# H_bridge.net
KiCad netlist of a schematic drawn in Altium Designer
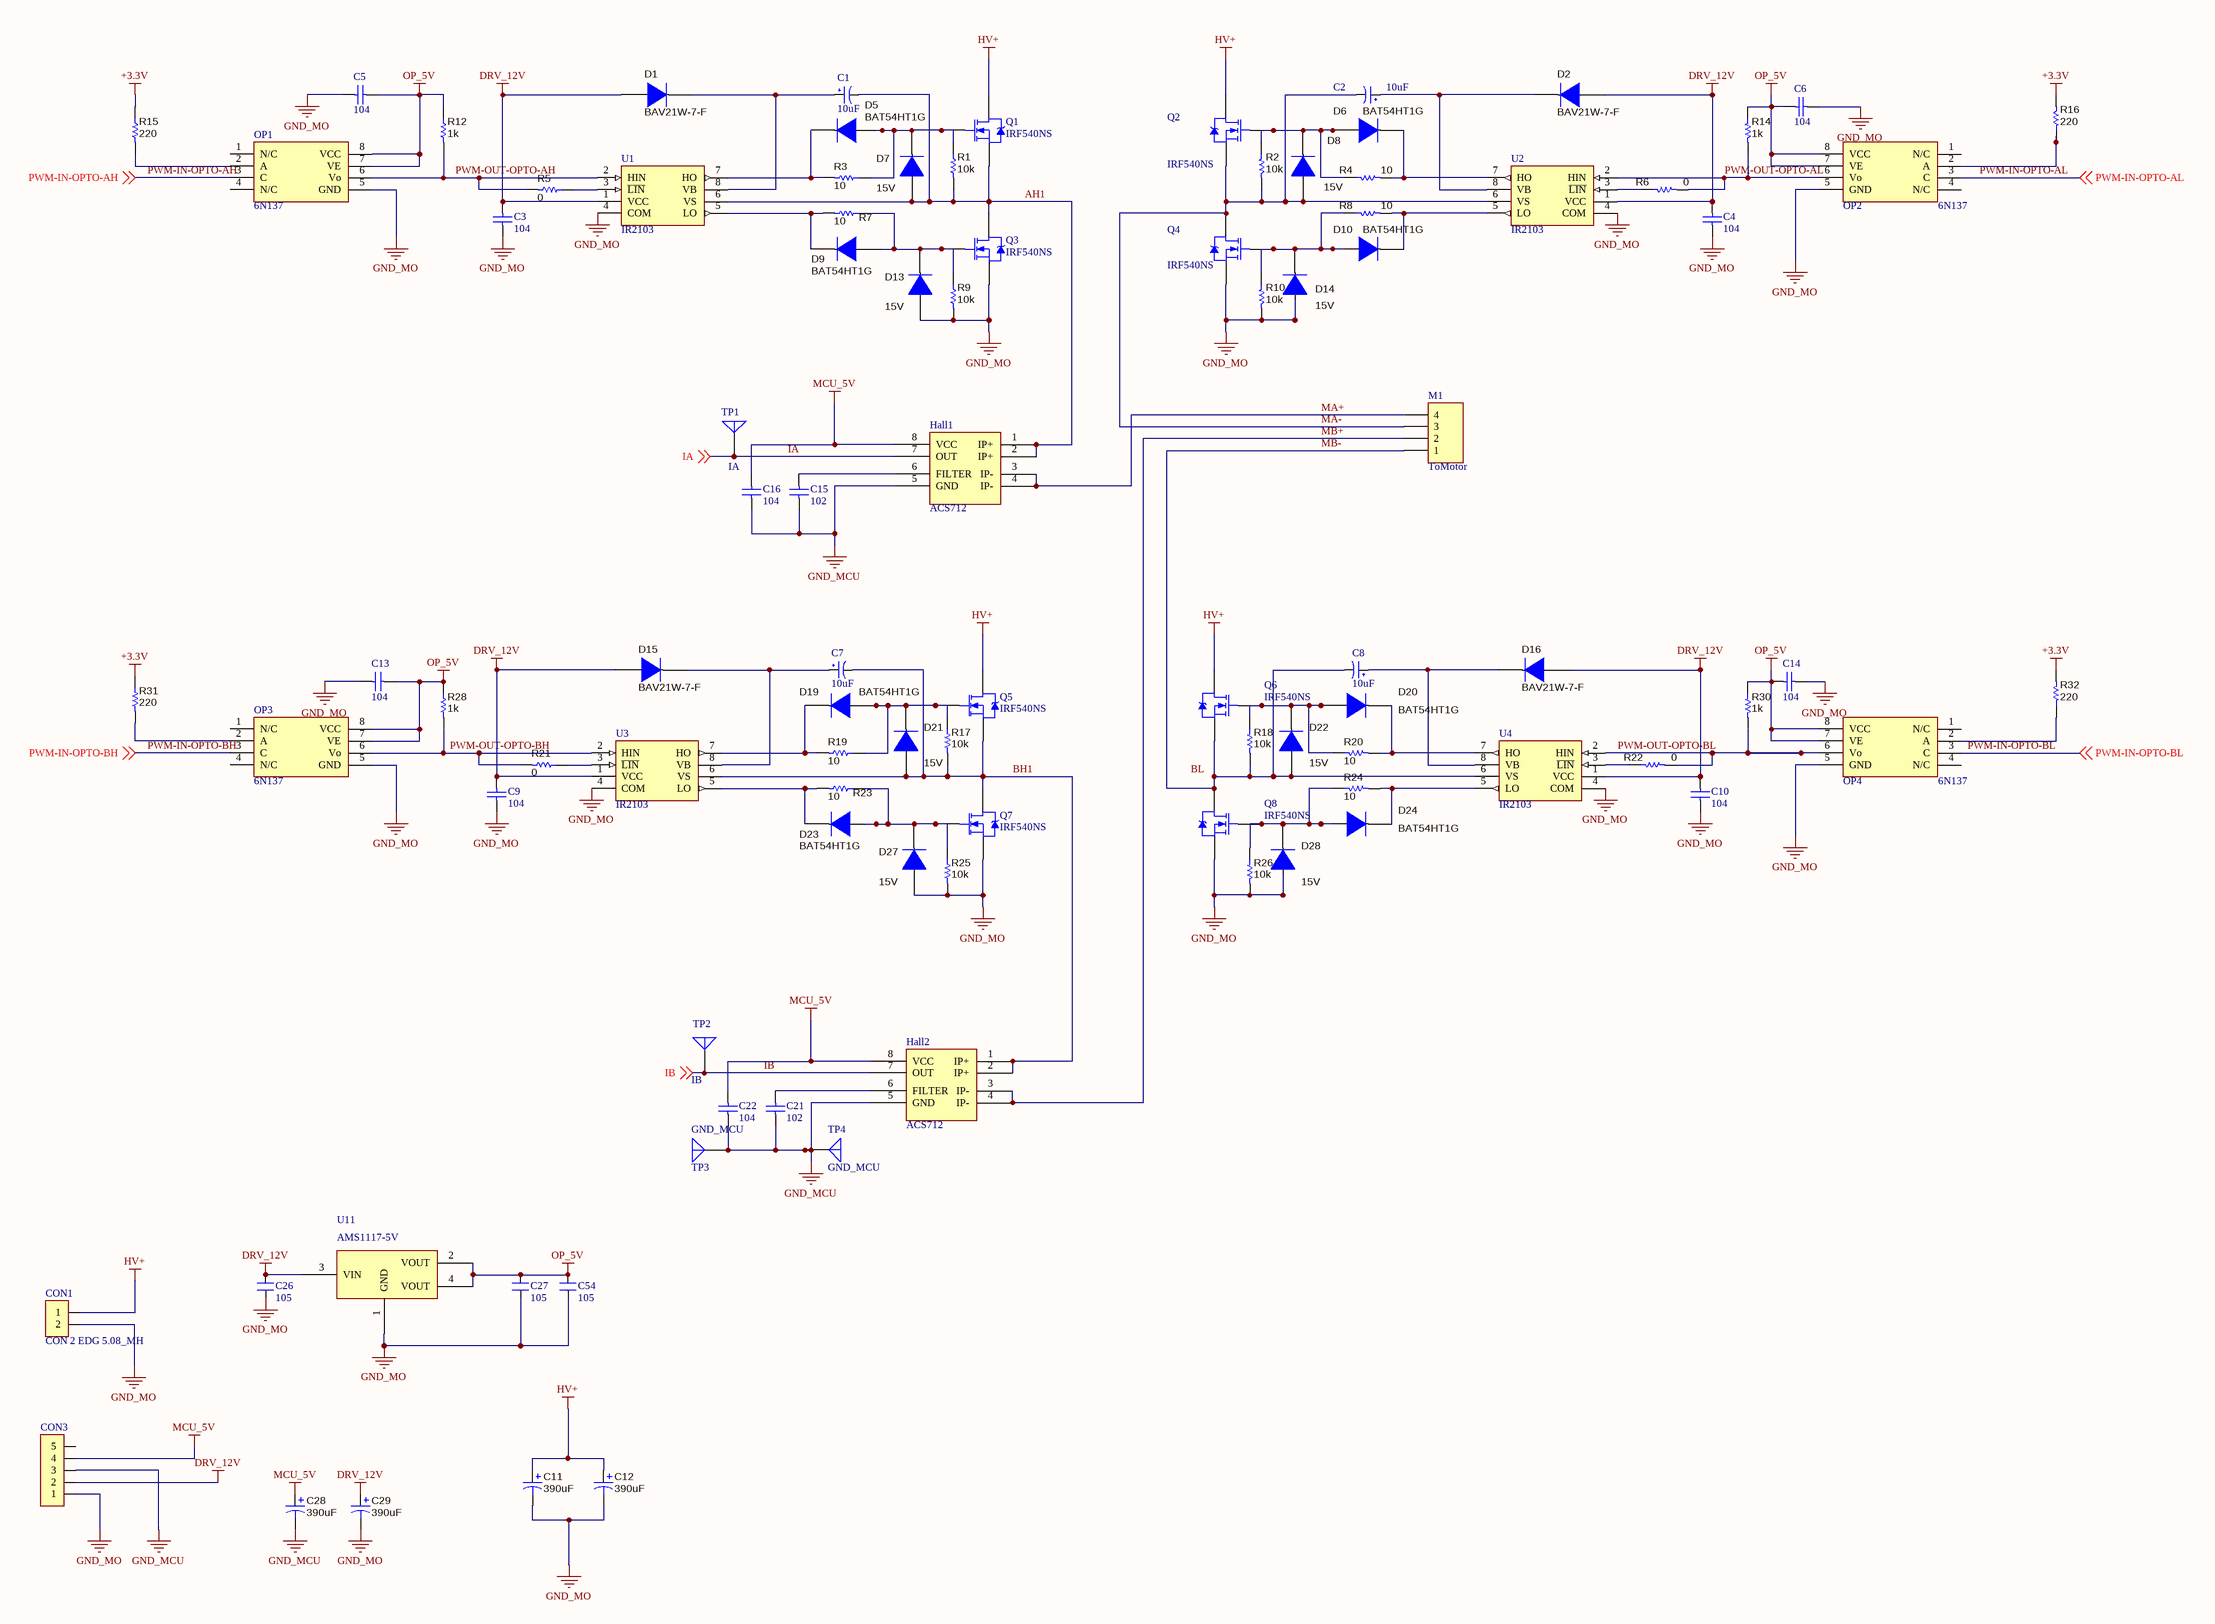
[diagram p0: H_bridge.SchDoc]

(export (version "E")
  (design (tool "Eeschema 10.0.6"))
  (components
    (comp (ref "C1")
      (value "10uF")
      (footprint "TU_NHOM_10uF_MH")
      (description "TU_NHOM_10uF_25V_MH")
      (libsource (lib "MH_DA_THU_VIEN_16122016") (part "TU_NHOM_10uF_25V_MH"))
    )
    (comp (ref "C2")
      (value "10uF")
      (footprint "TU_NHOM_10uF_MH")
      (description "TU_NHOM_10uF_25V_MH")
      (libsource (lib "MH_DA_THU_VIEN_16122016") (part "TU_NHOM_10uF_25V_MH"))
    )
    (comp (ref "C3")
      (value "104")
      (footprint "TU_SMD_0805")
      (description "Ceramic Chip Capacitor - Standard")
      (fields (field (name "PUBLISHER") "Altium Limited"))
      (libsource (lib "mySch") (part "Capacitor 0805"))
    )
    (comp (ref "C4")
      (value "104")
      (footprint "TU_SMD_0805")
      (description "Ceramic Chip Capacitor - Standard")
      (fields (field (name "PUBLISHER") "Altium Limited"))
      (libsource (lib "mySch") (part "Capacitor 0805"))
    )
    (comp (ref "C5")
      (value "104")
      (footprint "TU_SMD_0805")
      (description "Ceramic Chip Capacitor - Standard")
      (fields (field (name "PUBLISHER") "Altium Limited"))
      (libsource (lib "mySch") (part "Capacitor 0805"))
    )
    (comp (ref "C6")
      (value "104")
      (footprint "TU_SMD_0805")
      (description "Ceramic Chip Capacitor - Standard")
      (fields (field (name "PUBLISHER") "Altium Limited"))
      (libsource (lib "mySch") (part "Capacitor 0805"))
    )
    (comp (ref "C7")
      (value "10uF")
      (footprint "TU_NHOM_10uF_MH")
      (description "TU_NHOM_10uF_25V_MH")
      (libsource (lib "MH_DA_THU_VIEN_16122016") (part "TU_NHOM_10uF_25V_MH"))
    )
    (comp (ref "C8")
      (value "10uF")
      (footprint "TU_NHOM_10uF_MH")
      (description "TU_NHOM_10uF_25V_MH")
      (libsource (lib "MH_DA_THU_VIEN_16122016") (part "TU_NHOM_10uF_25V_MH"))
    )
    (comp (ref "C9")
      (value "104")
      (footprint "TU_SMD_0805")
      (description "Ceramic Chip Capacitor - Standard")
      (fields (field (name "PUBLISHER") "Altium Limited"))
      (libsource (lib "mySch") (part "Capacitor 0805"))
    )
    (comp (ref "C10")
      (value "104")
      (footprint "TU_SMD_0805")
      (description "Ceramic Chip Capacitor - Standard")
      (fields (field (name "PUBLISHER") "Altium Limited"))
      (libsource (lib "mySch") (part "Capacitor 0805"))
    )
    (comp (ref "C11")
      (value "390uF")
      (footprint "CAP_12.5 X 25")
      (description "CAP ALUM 390UF 20% 50V RADIAL")
      (fields
        (field (name "PARTNUMBER") "UHW1H391MPD6")
        (field (name "MANUFACTURER") "Nichicon")
        (field (name "VALUEDISPLAYED") "390uF")
        (field (name "PUBLISHER") "Texas Instruments")
      )
      (libsource (lib "mySch") (part "Capacitor TuHoa"))
    )
    (comp (ref "C12")
      (value "390uF")
      (footprint "CAP_12.5 X 25")
      (description "CAP ALUM 390UF 20% 50V RADIAL")
      (fields
        (field (name "PARTNUMBER") "UHW1H391MPD6")
        (field (name "MANUFACTURER") "Nichicon")
        (field (name "VALUEDISPLAYED") "390uF")
        (field (name "PUBLISHER") "Texas Instruments")
      )
      (libsource (lib "mySch") (part "Capacitor TuHoa"))
    )
    (comp (ref "C13")
      (value "104")
      (footprint "TU_SMD_0805")
      (description "Ceramic Chip Capacitor - Standard")
      (fields (field (name "PUBLISHER") "Altium Limited"))
      (libsource (lib "mySch") (part "Capacitor 0805"))
    )
    (comp (ref "C14")
      (value "104")
      (footprint "TU_SMD_0805")
      (description "Ceramic Chip Capacitor - Standard")
      (fields (field (name "PUBLISHER") "Altium Limited"))
      (libsource (lib "mySch") (part "Capacitor 0805"))
    )
    (comp (ref "C15")
      (value "102")
      (footprint "TU_SMD_0805")
      (description "Ceramic Chip Capacitor - Standard")
      (fields (field (name "PUBLISHER") "Altium Limited"))
      (libsource (lib "mySch") (part "Capacitor 0805"))
    )
    (comp (ref "C16")
      (value "104")
      (footprint "TU_SMD_0805")
      (description "Ceramic Chip Capacitor - Standard")
      (fields (field (name "PUBLISHER") "Altium Limited"))
      (libsource (lib "mySch") (part "Capacitor 0805"))
    )
    (comp (ref "C21")
      (value "102")
      (footprint "TU_SMD_0805")
      (description "Ceramic Chip Capacitor - Standard")
      (fields (field (name "PUBLISHER") "Altium Limited"))
      (libsource (lib "mySch") (part "Capacitor 0805"))
    )
    (comp (ref "C22")
      (value "104")
      (footprint "TU_SMD_0805")
      (description "Ceramic Chip Capacitor - Standard")
      (fields (field (name "PUBLISHER") "Altium Limited"))
      (libsource (lib "mySch") (part "Capacitor 0805"))
    )
    (comp (ref "C26")
      (value "105")
      (footprint "0805_HV")
      (description "Cap SMD")
      (libsource (lib "hatcatbietbay") (part "CM"))
    )
    (comp (ref "C27")
      (value "105")
      (footprint "0805_HV")
      (description "Cap SMD")
      (libsource (lib "hatcatbietbay") (part "CM"))
    )
    (comp (ref "C28")
      (value "390uF")
      (footprint "CP1/3.0")
      (fields
        (field (name "PARTNUMBER") "UHW1H391MPD6")
        (field (name "MANUFACTURER") "Nichicon")
        (field (name "VALUEDISPLAYED") "390uF")
        (field (name "PUBLISHER") "Texas Instruments")
      )
      (libsource (lib "mySch") (part "Capacitor TuHoa"))
    )
    (comp (ref "C29")
      (value "390uF")
      (footprint "CP1/3.0")
      (fields
        (field (name "PARTNUMBER") "UHW1H391MPD6")
        (field (name "MANUFACTURER") "Nichicon")
        (field (name "VALUEDISPLAYED") "390uF")
        (field (name "PUBLISHER") "Texas Instruments")
      )
      (libsource (lib "mySch") (part "Capacitor TuHoa"))
    )
    (comp (ref "C54")
      (value "105")
      (footprint "0805_HV")
      (description "Cap SMD")
      (libsource (lib "hatcatbietbay") (part "CM"))
    )
    (comp (ref "CON1")
      (value "CON 2 EDG 5.08_MH")
      (footprint "CON 2 EDG 5.08")
      (description "CON 2 EDG 5.08 (xanh cong)")
      (libsource (lib "mySch") (part "CON 2 EDG 5.08_MH"))
    )
    (comp (ref "CON3")
      (value "CON 5 EDG 5.08_MH")
      (footprint "Con 5 EDG 5.08")
      (description "CON 5 EDG 5.08 (xanh cong)")
      (libsource (lib "MH_DA_THU_VIEN_16122016") (part "CON 5 EDG 5.08_MH"))
    )
    (comp (ref "D1")
      (value "BAV21W-7-F")
      (footprint "SOD-323")
      (description "Diode, Switching, 100 V, 0.2 A, SOD-323")
      (fields
        (field (name "MANUFACTURER") "Micro Commercial Components")
        (field (name "PUBLISHER") "Texas Instruments")
      )
      (libsource (lib "Diode") (part "MMDL914-TP"))
    )
    (comp (ref "D2")
      (value "BAV21W-7-F")
      (footprint "SOD-323")
      (description "Diode, Switching, 100 V, 0.2 A, SOD-323")
      (fields
        (field (name "MANUFACTURER") "Micro Commercial Components")
        (field (name "PUBLISHER") "Texas Instruments")
      )
      (libsource (lib "Diode") (part "MMDL914-TP"))
    )
    (comp (ref "D5")
      (value "BAT54HT1G")
      (footprint "SOD-323")
      (description "Diode, Switching, 100 V, 0.2 A, SOD-323")
      (fields
        (field (name "MANUFACTURER") "Micro Commercial Components")
        (field (name "PUBLISHER") "Texas Instruments")
      )
      (libsource (lib "Diode") (part "MMDL914-TP"))
    )
    (comp (ref "D6")
      (value "BAT54HT1G")
      (footprint "SOD-323")
      (description "Diode, Switching, 100 V, 0.2 A, SOD-323")
      (fields
        (field (name "MANUFACTURER") "Micro Commercial Components")
        (field (name "PUBLISHER") "Texas Instruments")
      )
      (libsource (lib "Diode") (part "MMDL914-TP"))
    )
    (comp (ref "D7")
      (value "15V")
      (footprint "SOD-323")
      (description "Diode, Switching, 100 V, 0.2 A, SOD-323")
      (fields
        (field (name "PARTNUMBER") "BAV21W-7-F")
        (field (name "MANUFACTURER") "Micro Commercial Components")
        (field (name "PUBLISHER") "Texas Instruments")
      )
      (libsource (lib "Diode") (part "MMDL914-TP"))
    )
    (comp (ref "D8")
      (value "15V")
      (footprint "SOD-323")
      (description "Diode, Switching, 100 V, 0.2 A, SOD-323")
      (fields
        (field (name "PARTNUMBER") "BAV21W-7-F")
        (field (name "MANUFACTURER") "Micro Commercial Components")
        (field (name "PUBLISHER") "Texas Instruments")
      )
      (libsource (lib "Diode") (part "MMDL914-TP"))
    )
    (comp (ref "D9")
      (value "BAT54HT1G")
      (footprint "SOD-323")
      (description "Diode, Switching, 100 V, 0.2 A, SOD-323")
      (fields
        (field (name "MANUFACTURER") "Micro Commercial Components")
        (field (name "PUBLISHER") "Texas Instruments")
      )
      (libsource (lib "Diode") (part "MMDL914-TP"))
    )
    (comp (ref "D10")
      (value "BAT54HT1G")
      (footprint "SOD-323")
      (description "Diode, Switching, 100 V, 0.2 A, SOD-323")
      (fields
        (field (name "MANUFACTURER") "Micro Commercial Components")
        (field (name "PUBLISHER") "Texas Instruments")
      )
      (libsource (lib "Diode") (part "MMDL914-TP"))
    )
    (comp (ref "D13")
      (value "15V")
      (footprint "SOD-323")
      (description "Diode, Switching, 100 V, 0.2 A, SOD-323")
      (fields
        (field (name "PARTNUMBER") "BAV21W-7-F")
        (field (name "MANUFACTURER") "Micro Commercial Components")
        (field (name "PUBLISHER") "Texas Instruments")
      )
      (libsource (lib "Diode") (part "MMDL914-TP"))
    )
    (comp (ref "D14")
      (value "15V")
      (footprint "SOD-323")
      (description "Diode, Switching, 100 V, 0.2 A, SOD-323")
      (fields
        (field (name "PARTNUMBER") "BAV21W-7-F")
        (field (name "MANUFACTURER") "Micro Commercial Components")
        (field (name "PUBLISHER") "Texas Instruments")
      )
      (libsource (lib "Diode") (part "MMDL914-TP"))
    )
    (comp (ref "D15")
      (value "BAV21W-7-F")
      (footprint "SOD-323")
      (description "Diode, Switching, 100 V, 0.2 A, SOD-323")
      (fields
        (field (name "MANUFACTURER") "Micro Commercial Components")
        (field (name "PUBLISHER") "Texas Instruments")
      )
      (libsource (lib "Diode") (part "MMDL914-TP"))
    )
    (comp (ref "D16")
      (value "BAV21W-7-F")
      (footprint "SOD-323")
      (description "Diode, Switching, 100 V, 0.2 A, SOD-323")
      (fields
        (field (name "MANUFACTURER") "Micro Commercial Components")
        (field (name "PUBLISHER") "Texas Instruments")
      )
      (libsource (lib "Diode") (part "MMDL914-TP"))
    )
    (comp (ref "D19")
      (value "BAT54HT1G")
      (footprint "SOD-323")
      (description "Diode, Switching, 100 V, 0.2 A, SOD-323")
      (fields
        (field (name "MANUFACTURER") "Micro Commercial Components")
        (field (name "PUBLISHER") "Texas Instruments")
      )
      (libsource (lib "Diode") (part "MMDL914-TP"))
    )
    (comp (ref "D20")
      (value "BAT54HT1G")
      (footprint "SOD-323")
      (description "Diode, Switching, 100 V, 0.2 A, SOD-323")
      (fields
        (field (name "MANUFACTURER") "Micro Commercial Components")
        (field (name "PUBLISHER") "Texas Instruments")
      )
      (libsource (lib "Diode") (part "MMDL914-TP"))
    )
    (comp (ref "D21")
      (value "15V")
      (footprint "SOD-323")
      (description "Diode, Switching, 100 V, 0.2 A, SOD-323")
      (fields
        (field (name "PARTNUMBER") "BAV21W-7-F")
        (field (name "MANUFACTURER") "Micro Commercial Components")
        (field (name "PUBLISHER") "Texas Instruments")
      )
      (libsource (lib "Diode") (part "MMDL914-TP"))
    )
    (comp (ref "D22")
      (value "15V")
      (footprint "SOD-323")
      (description "Diode, Switching, 100 V, 0.2 A, SOD-323")
      (fields
        (field (name "PARTNUMBER") "BAV21W-7-F")
        (field (name "MANUFACTURER") "Micro Commercial Components")
        (field (name "PUBLISHER") "Texas Instruments")
      )
      (libsource (lib "Diode") (part "MMDL914-TP"))
    )
    (comp (ref "D23")
      (value "BAT54HT1G")
      (footprint "SOD-323")
      (description "Diode, Switching, 100 V, 0.2 A, SOD-323")
      (fields
        (field (name "MANUFACTURER") "Micro Commercial Components")
        (field (name "PUBLISHER") "Texas Instruments")
      )
      (libsource (lib "Diode") (part "MMDL914-TP"))
    )
    (comp (ref "D24")
      (value "BAT54HT1G")
      (footprint "SOD-323")
      (description "Diode, Switching, 100 V, 0.2 A, SOD-323")
      (fields
        (field (name "MANUFACTURER") "Micro Commercial Components")
        (field (name "PUBLISHER") "Texas Instruments")
      )
      (libsource (lib "Diode") (part "MMDL914-TP"))
    )
    (comp (ref "D27")
      (value "15V")
      (footprint "SOD-323")
      (description "Diode, Switching, 100 V, 0.2 A, SOD-323")
      (fields
        (field (name "PARTNUMBER") "BAV21W-7-F")
        (field (name "MANUFACTURER") "Micro Commercial Components")
        (field (name "PUBLISHER") "Texas Instruments")
      )
      (libsource (lib "Diode") (part "MMDL914-TP"))
    )
    (comp (ref "D28")
      (value "15V")
      (footprint "SOD-323")
      (description "Diode, Switching, 100 V, 0.2 A, SOD-323")
      (fields
        (field (name "PARTNUMBER") "BAV21W-7-F")
        (field (name "MANUFACTURER") "Micro Commercial Components")
        (field (name "PUBLISHER") "Texas Instruments")
      )
      (libsource (lib "Diode") (part "MMDL914-TP"))
    )
    (comp (ref "Hall1") (value "ACS712") (footprint "SOP 8") (libsource (lib "mySch") (part "ACS712")))
    (comp (ref "Hall2") (value "ACS712") (footprint "SOP 8") (libsource (lib "mySch") (part "ACS712")))
    (comp (ref "M1")
      (value "ToMotor")
      (footprint "Con 4 EDG 5.08")
      (description "Header, 4-Pin")
      (fields (field (name "PUBLISHER") "Altium Limited"))
      (libsource (lib "Miscellaneous Connectors") (part "Header 4"))
    )
    (comp (ref "OP1")
      (value "6N137 DIP8 Opto 10Mbit")
      (footprint "SMD-8_6.3MM")
      (description "6N137 DIP8 Opto 10Mbit/s")
      (libsource (lib "mySch") (part "6N137"))
    )
    (comp (ref "OP2")
      (value "6N137 DIP8 Opto 10Mbit")
      (footprint "SMD-8_6.3MM")
      (description "6N137 DIP8 Opto 10Mbit/s")
      (libsource (lib "") (part "6N137_1"))
    )
    (comp (ref "OP3")
      (value "6N137 DIP8 Opto 10Mbit")
      (footprint "SMD-8_6.3MM")
      (description "6N137 DIP8 Opto 10Mbit/s")
      (libsource (lib "mySch") (part "6N137"))
    )
    (comp (ref "OP4")
      (value "6N137 DIP8 Opto 10Mbit")
      (footprint "SMD-8_6.3MM")
      (description "6N137 DIP8 Opto 10Mbit/s")
      (libsource (lib "") (part "6N137_1"))
    )
    (comp (ref "Q1")
      (value "IRF540NS")
      (footprint "D2PAK_M_1")
      (description "HEXFET Power MOSFET")
      (fields (field (name "PUBLISHER") "Altium Limited"))
      (libsource (lib "mySch") (part "IRF540NS"))
    )
    (comp (ref "Q2")
      (value "IRF540NS")
      (footprint "D2PAK_M_1")
      (description "HEXFET Power MOSFET")
      (fields (field (name "PUBLISHER") "Altium Limited"))
      (libsource (lib "mySch") (part "IRF540NS"))
    )
    (comp (ref "Q3")
      (value "IRF540NS")
      (footprint "D2PAK_M_1")
      (description "HEXFET Power MOSFET")
      (fields (field (name "PUBLISHER") "Altium Limited"))
      (libsource (lib "mySch") (part "IRF540NS"))
    )
    (comp (ref "Q4")
      (value "IRF540NS")
      (footprint "D2PAK_M_1")
      (description "HEXFET Power MOSFET")
      (fields (field (name "PUBLISHER") "Altium Limited"))
      (libsource (lib "mySch") (part "IRF540NS"))
    )
    (comp (ref "Q5")
      (value "IRF540NS")
      (footprint "D2PAK_M_1")
      (description "HEXFET Power MOSFET")
      (fields (field (name "PUBLISHER") "Altium Limited"))
      (libsource (lib "mySch") (part "IRF540NS"))
    )
    (comp (ref "Q6")
      (value "IRF540NS")
      (footprint "D2PAK_M_1")
      (description "HEXFET Power MOSFET")
      (fields (field (name "PUBLISHER") "Altium Limited"))
      (libsource (lib "mySch") (part "IRF540NS"))
    )
    (comp (ref "Q7")
      (value "IRF540NS")
      (footprint "D2PAK_M_1")
      (description "HEXFET Power MOSFET")
      (fields (field (name "PUBLISHER") "Altium Limited"))
      (libsource (lib "mySch") (part "IRF540NS"))
    )
    (comp (ref "Q8")
      (value "IRF540NS")
      (footprint "D2PAK_M_1")
      (description "HEXFET Power MOSFET")
      (fields (field (name "PUBLISHER") "Altium Limited"))
      (libsource (lib "mySch") (part "IRF540NS"))
    )
    (comp (ref "R1")
      (value "10k")
      (footprint "Tro SMD 0805")
      (description "RES, 100, 1%, 0.1 W, 0402")
      (fields
        (field (name "PARTNUMBER") "ERJ-2RKF1000X")
        (field (name "MANUFACTURER") "Panasonic")
        (field (name "PUBLISHER") "Texas Instruments")
      )
      (libsource (lib "mySch") (part "R nho"))
    )
    (comp (ref "R2")
      (value "10k")
      (footprint "Tro SMD 0805")
      (description "RES, 100, 1%, 0.1 W, 0402")
      (fields
        (field (name "PARTNUMBER") "ERJ-2RKF1000X")
        (field (name "MANUFACTURER") "Panasonic")
        (field (name "PUBLISHER") "Texas Instruments")
      )
      (libsource (lib "mySch") (part "R nho"))
    )
    (comp (ref "R3")
      (value "10")
      (footprint "Tro SMD 0805")
      (description "RES, 100, 1%, 0.1 W, 0402")
      (fields
        (field (name "PARTNUMBER") "ERJ-2RKF1000X")
        (field (name "MANUFACTURER") "Panasonic")
        (field (name "PUBLISHER") "Texas Instruments")
      )
      (libsource (lib "mySch") (part "R nho"))
    )
    (comp (ref "R4")
      (value "10")
      (footprint "Tro SMD 0805")
      (description "RES, 100, 1%, 0.1 W, 0402")
      (fields
        (field (name "PARTNUMBER") "ERJ-2RKF1000X")
        (field (name "MANUFACTURER") "Panasonic")
        (field (name "PUBLISHER") "Texas Instruments")
      )
      (libsource (lib "mySch") (part "R nho"))
    )
    (comp (ref "R5")
      (value "0")
      (footprint "Tro SMD 0805")
      (description "RES, 100, 1%, 0.1 W, 0402")
      (fields
        (field (name "PARTNUMBER") "ERJ-2RKF1000X")
        (field (name "MANUFACTURER") "Panasonic")
        (field (name "PUBLISHER") "Texas Instruments")
      )
      (libsource (lib "mySch") (part "R nho"))
    )
    (comp (ref "R6")
      (value "0")
      (footprint "Tro SMD 0805")
      (description "RES, 100, 1%, 0.1 W, 0402")
      (fields
        (field (name "PARTNUMBER") "ERJ-2RKF1000X")
        (field (name "MANUFACTURER") "Panasonic")
        (field (name "PUBLISHER") "Texas Instruments")
      )
      (libsource (lib "mySch") (part "R nho"))
    )
    (comp (ref "R7")
      (value "10")
      (footprint "Tro SMD 0805")
      (description "RES, 100, 1%, 0.1 W, 0402")
      (fields
        (field (name "PARTNUMBER") "ERJ-2RKF1000X")
        (field (name "MANUFACTURER") "Panasonic")
        (field (name "PUBLISHER") "Texas Instruments")
      )
      (libsource (lib "mySch") (part "R nho"))
    )
    (comp (ref "R8")
      (value "10")
      (footprint "Tro SMD 0805")
      (description "RES, 100, 1%, 0.1 W, 0402")
      (fields
        (field (name "PARTNUMBER") "ERJ-2RKF1000X")
        (field (name "MANUFACTURER") "Panasonic")
        (field (name "PUBLISHER") "Texas Instruments")
      )
      (libsource (lib "mySch") (part "R nho"))
    )
    (comp (ref "R9")
      (value "10k")
      (footprint "Tro SMD 0805")
      (description "RES, 100, 1%, 0.1 W, 0402")
      (fields
        (field (name "PARTNUMBER") "ERJ-2RKF1000X")
        (field (name "MANUFACTURER") "Panasonic")
        (field (name "PUBLISHER") "Texas Instruments")
      )
      (libsource (lib "mySch") (part "R nho"))
    )
    (comp (ref "R10")
      (value "10k")
      (footprint "Tro SMD 0805")
      (description "RES, 100, 1%, 0.1 W, 0402")
      (fields
        (field (name "PARTNUMBER") "ERJ-2RKF1000X")
        (field (name "MANUFACTURER") "Panasonic")
        (field (name "PUBLISHER") "Texas Instruments")
      )
      (libsource (lib "mySch") (part "R nho"))
    )
    (comp (ref "R12")
      (value "1k")
      (footprint "Tro SMD 0805")
      (description "RES, 100, 1%, 0.1 W, 0402")
      (fields
        (field (name "PARTNUMBER") "ERJ-2RKF1000X")
        (field (name "MANUFACTURER") "Panasonic")
        (field (name "PUBLISHER") "Texas Instruments")
      )
      (libsource (lib "mySch") (part "R nho"))
    )
    (comp (ref "R14")
      (value "1k")
      (footprint "Tro SMD 0805")
      (description "RES, 100, 1%, 0.1 W, 0402")
      (fields
        (field (name "PARTNUMBER") "ERJ-2RKF1000X")
        (field (name "MANUFACTURER") "Panasonic")
        (field (name "PUBLISHER") "Texas Instruments")
      )
      (libsource (lib "mySch") (part "R nho"))
    )
    (comp (ref "R15")
      (value "220")
      (footprint "Tro SMD 0805")
      (description "RES, 100, 1%, 0.1 W, 0402")
      (fields
        (field (name "PARTNUMBER") "ERJ-2RKF1000X")
        (field (name "MANUFACTURER") "Panasonic")
        (field (name "PUBLISHER") "Texas Instruments")
      )
      (libsource (lib "mySch") (part "R nho"))
    )
    (comp (ref "R16")
      (value "220")
      (footprint "Tro SMD 0805")
      (description "RES, 100, 1%, 0.1 W, 0402")
      (fields
        (field (name "PARTNUMBER") "ERJ-2RKF1000X")
        (field (name "MANUFACTURER") "Panasonic")
        (field (name "PUBLISHER") "Texas Instruments")
      )
      (libsource (lib "mySch") (part "R nho"))
    )
    (comp (ref "R17")
      (value "10k")
      (footprint "Tro SMD 0805")
      (description "RES, 100, 1%, 0.1 W, 0402")
      (fields
        (field (name "PARTNUMBER") "ERJ-2RKF1000X")
        (field (name "MANUFACTURER") "Panasonic")
        (field (name "PUBLISHER") "Texas Instruments")
      )
      (libsource (lib "mySch") (part "R nho"))
    )
    (comp (ref "R18")
      (value "10k")
      (footprint "Tro SMD 0805")
      (description "RES, 100, 1%, 0.1 W, 0402")
      (fields
        (field (name "PARTNUMBER") "ERJ-2RKF1000X")
        (field (name "MANUFACTURER") "Panasonic")
        (field (name "PUBLISHER") "Texas Instruments")
      )
      (libsource (lib "mySch") (part "R nho"))
    )
    (comp (ref "R19")
      (value "10")
      (footprint "Tro SMD 0805")
      (description "RES, 100, 1%, 0.1 W, 0402")
      (fields
        (field (name "PARTNUMBER") "ERJ-2RKF1000X")
        (field (name "MANUFACTURER") "Panasonic")
        (field (name "PUBLISHER") "Texas Instruments")
      )
      (libsource (lib "mySch") (part "R nho"))
    )
    (comp (ref "R20")
      (value "10")
      (footprint "Tro SMD 0805")
      (description "RES, 100, 1%, 0.1 W, 0402")
      (fields
        (field (name "PARTNUMBER") "ERJ-2RKF1000X")
        (field (name "MANUFACTURER") "Panasonic")
        (field (name "PUBLISHER") "Texas Instruments")
      )
      (libsource (lib "mySch") (part "R nho"))
    )
    (comp (ref "R21")
      (value "0")
      (footprint "Tro SMD 0805")
      (description "RES, 100, 1%, 0.1 W, 0402")
      (fields
        (field (name "PARTNUMBER") "ERJ-2RKF1000X")
        (field (name "MANUFACTURER") "Panasonic")
        (field (name "PUBLISHER") "Texas Instruments")
      )
      (libsource (lib "mySch") (part "R nho"))
    )
    (comp (ref "R22")
      (value "0")
      (footprint "Tro SMD 0805")
      (description "RES, 100, 1%, 0.1 W, 0402")
      (fields
        (field (name "PARTNUMBER") "ERJ-2RKF1000X")
        (field (name "MANUFACTURER") "Panasonic")
        (field (name "PUBLISHER") "Texas Instruments")
      )
      (libsource (lib "mySch") (part "R nho"))
    )
    (comp (ref "R23")
      (value "10")
      (footprint "Tro SMD 0805")
      (description "RES, 100, 1%, 0.1 W, 0402")
      (fields
        (field (name "PARTNUMBER") "ERJ-2RKF1000X")
        (field (name "MANUFACTURER") "Panasonic")
        (field (name "PUBLISHER") "Texas Instruments")
      )
      (libsource (lib "mySch") (part "R nho"))
    )
    (comp (ref "R24")
      (value "10")
      (footprint "Tro SMD 0805")
      (description "RES, 100, 1%, 0.1 W, 0402")
      (fields
        (field (name "PARTNUMBER") "ERJ-2RKF1000X")
        (field (name "MANUFACTURER") "Panasonic")
        (field (name "PUBLISHER") "Texas Instruments")
      )
      (libsource (lib "mySch") (part "R nho"))
    )
    (comp (ref "R25")
      (value "10k")
      (footprint "Tro SMD 0805")
      (description "RES, 100, 1%, 0.1 W, 0402")
      (fields
        (field (name "PARTNUMBER") "ERJ-2RKF1000X")
        (field (name "MANUFACTURER") "Panasonic")
        (field (name "PUBLISHER") "Texas Instruments")
      )
      (libsource (lib "mySch") (part "R nho"))
    )
    (comp (ref "R26")
      (value "10k")
      (footprint "Tro SMD 0805")
      (description "RES, 100, 1%, 0.1 W, 0402")
      (fields
        (field (name "PARTNUMBER") "ERJ-2RKF1000X")
        (field (name "MANUFACTURER") "Panasonic")
        (field (name "PUBLISHER") "Texas Instruments")
      )
      (libsource (lib "mySch") (part "R nho"))
    )
    (comp (ref "R28")
      (value "1k")
      (footprint "Tro SMD 0805")
      (description "RES, 100, 1%, 0.1 W, 0402")
      (fields
        (field (name "PARTNUMBER") "ERJ-2RKF1000X")
        (field (name "MANUFACTURER") "Panasonic")
        (field (name "PUBLISHER") "Texas Instruments")
      )
      (libsource (lib "mySch") (part "R nho"))
    )
    (comp (ref "R30")
      (value "1k")
      (footprint "Tro SMD 0805")
      (description "RES, 100, 1%, 0.1 W, 0402")
      (fields
        (field (name "PARTNUMBER") "ERJ-2RKF1000X")
        (field (name "MANUFACTURER") "Panasonic")
        (field (name "PUBLISHER") "Texas Instruments")
      )
      (libsource (lib "mySch") (part "R nho"))
    )
    (comp (ref "R31")
      (value "220")
      (footprint "Tro SMD 0805")
      (description "RES, 100, 1%, 0.1 W, 0402")
      (fields
        (field (name "PARTNUMBER") "ERJ-2RKF1000X")
        (field (name "MANUFACTURER") "Panasonic")
        (field (name "PUBLISHER") "Texas Instruments")
      )
      (libsource (lib "mySch") (part "R nho"))
    )
    (comp (ref "R32")
      (value "220")
      (footprint "Tro SMD 0805")
      (description "RES, 100, 1%, 0.1 W, 0402")
      (fields
        (field (name "PARTNUMBER") "ERJ-2RKF1000X")
        (field (name "MANUFACTURER") "Panasonic")
        (field (name "PUBLISHER") "Texas Instruments")
      )
      (libsource (lib "mySch") (part "R nho"))
    )
    (comp (ref "TP1")
      (value "IA")
      (footprint "PIN1")
      (description "Generic Antenna")
      (fields (field (name "PUBLISHER") "Altium Limited"))
      (libsource (lib "Miscellaneous Devices") (part "Antenna"))
    )
    (comp (ref "TP2")
      (value "IB")
      (footprint "PIN1")
      (description "Generic Antenna")
      (fields (field (name "PUBLISHER") "Altium Limited"))
      (libsource (lib "Miscellaneous Devices") (part "Antenna"))
    )
    (comp (ref "TP3")
      (value "GND_MCU")
      (footprint "PIN1")
      (description "Generic Antenna")
      (fields (field (name "PUBLISHER") "Altium Limited"))
      (libsource (lib "Miscellaneous Devices") (part "Antenna"))
    )
    (comp (ref "TP4")
      (value "GND_MCU")
      (footprint "PIN1")
      (description "Generic Antenna")
      (fields (field (name "PUBLISHER") "Altium Limited"))
      (libsource (lib "Miscellaneous Devices") (part "Antenna"))
    )
    (comp (ref "U1")
      (value "IR2103")
      (footprint "SOP 8")
      (description "High and Low Side Driver")
      (fields (field (name "PUBLISHER") "Altium Limited"))
      (libsource (lib "IR Interface Bridge Driver") (part "IR2103"))
    )
    (comp (ref "U2")
      (value "IR2103")
      (footprint "SOP 8")
      (description "High and Low Side Driver")
      (fields (field (name "PUBLISHER") "Altium Limited"))
      (libsource (lib "") (part "IR2103_1"))
    )
    (comp (ref "U3")
      (value "IR2103")
      (footprint "SOP 8")
      (description "High and Low Side Driver")
      (fields (field (name "PUBLISHER") "Altium Limited"))
      (libsource (lib "IR Interface Bridge Driver") (part "IR2103"))
    )
    (comp (ref "U4")
      (value "IR2103")
      (footprint "SOP 8")
      (description "High and Low Side Driver")
      (fields (field (name "PUBLISHER") "Altium Limited"))
      (libsource (lib "") (part "IR2103_1"))
    )
    (comp (ref "U11")
      (value "AMS1117-5V")
      (footprint "SOT223")
      (description "AMS1117-3.3V SOT223 _MH")
      (libsource (lib "MH_DA_THU_VIEN_16122016") (part "AMS1117-3.3V SOT223 _MH"))
    )
  )
  (nets
    (net (code "1") (name "+3.3V") (class "Default")
      (node (ref "R15") (pin "1") (pinfunction "1_1") (pintype "passive"))
      (node (ref "R16") (pin "2") (pinfunction "2_2") (pintype "passive"))
      (node (ref "R31") (pin "1") (pinfunction "1_1") (pintype "passive"))
      (node (ref "R32") (pin "2") (pinfunction "2_2") (pintype "passive"))
    )
    (net (code "2") (name "/AH1") (class "Default")
      (node (ref "C1") (pin "2") (pinfunction "2_2") (pintype "passive"))
      (node (ref "D7") (pin "2") (pinfunction "A_2") (pintype "passive"))
      (node (ref "Hall1") (pin "1") (pinfunction "IP+_1") (pintype "passive"))
      (node (ref "Hall1") (pin "2") (pinfunction "IP+_2") (pintype "passive"))
      (node (ref "Q1") (pin "3") (pinfunction "S_3") (pintype "passive"))
      (node (ref "Q3") (pin "2") (pinfunction "D_2") (pintype "passive"))
      (node (ref "R1") (pin "2") (pinfunction "2_2") (pintype "passive"))
      (node (ref "U1") (pin "6") (pinfunction "VS_6") (pintype "power_in"))
    )
    (net (code "3") (name "/BH1") (class "Default")
      (node (ref "C7") (pin "2") (pinfunction "2_2") (pintype "passive"))
      (node (ref "D21") (pin "2") (pinfunction "A_2") (pintype "passive"))
      (node (ref "Hall2") (pin "1") (pinfunction "IP+_1") (pintype "passive"))
      (node (ref "Hall2") (pin "2") (pinfunction "IP+_2") (pintype "passive"))
      (node (ref "Q5") (pin "3") (pinfunction "S_3") (pintype "passive"))
      (node (ref "Q7") (pin "2") (pinfunction "D_2") (pintype "passive"))
      (node (ref "R17") (pin "2") (pinfunction "2_2") (pintype "passive"))
      (node (ref "U3") (pin "6") (pinfunction "VS_6") (pintype "power_in"))
    )
    (net (code "5") (name "/MA+") (class "Default")
      (node (ref "Hall1") (pin "3") (pinfunction "IP-_3") (pintype "passive"))
      (node (ref "Hall1") (pin "4") (pinfunction "IP-_4") (pintype "passive"))
      (node (ref "M1") (pin "4") (pinfunction "4_4") (pintype "passive"))
    )
    (net (code "6") (name "/MA-") (class "Default")
      (node (ref "C2") (pin "2") (pinfunction "2_2") (pintype "passive"))
      (node (ref "D8") (pin "2") (pinfunction "A_2") (pintype "passive"))
      (node (ref "M1") (pin "3") (pinfunction "3_3") (pintype "passive"))
      (node (ref "Q2") (pin "3") (pinfunction "S_3") (pintype "passive"))
      (node (ref "Q4") (pin "2") (pinfunction "D_2") (pintype "passive"))
      (node (ref "R2") (pin "2") (pinfunction "2_2") (pintype "passive"))
      (node (ref "U2") (pin "6") (pinfunction "VS_6") (pintype "power_in"))
    )
    (net (code "7") (name "/MB+") (class "Default")
      (node (ref "Hall2") (pin "3") (pinfunction "IP-_3") (pintype "passive"))
      (node (ref "Hall2") (pin "4") (pinfunction "IP-_4") (pintype "passive"))
      (node (ref "M1") (pin "2") (pinfunction "2_2") (pintype "passive"))
    )
    (net (code "8") (name "/MB-") (class "Default")
      (node (ref "C8") (pin "2") (pinfunction "2_2") (pintype "passive"))
      (node (ref "D22") (pin "2") (pinfunction "A_2") (pintype "passive"))
      (node (ref "M1") (pin "1") (pinfunction "1_1") (pintype "passive"))
      (node (ref "Q6") (pin "3") (pinfunction "S_3") (pintype "passive"))
      (node (ref "Q8") (pin "2") (pinfunction "D_2") (pintype "passive"))
      (node (ref "R18") (pin "2") (pinfunction "2_2") (pintype "passive"))
      (node (ref "U4") (pin "6") (pinfunction "VS_6") (pintype "power_in"))
    )
    (net (code "9") (name "/PWM-OUT-OPTO-AH") (class "Default")
      (node (ref "OP1") (pin "6") (pinfunction "Vo_6") (pintype "passive"))
      (node (ref "R12") (pin "2") (pinfunction "2_2") (pintype "passive"))
      (node (ref "R5") (pin "2") (pinfunction "2_2") (pintype "passive"))
      (node (ref "U1") (pin "2") (pinfunction "HIN_2") (pintype "input"))
    )
    (net (code "10") (name "/PWM-OUT-OPTO-AL") (class "Default")
      (node (ref "OP2") (pin "6") (pinfunction "Vo_6") (pintype "passive"))
      (node (ref "R14") (pin "2") (pinfunction "2_2") (pintype "passive"))
      (node (ref "R6") (pin "2") (pinfunction "2_2") (pintype "passive"))
      (node (ref "U2") (pin "2") (pinfunction "HIN_2") (pintype "input"))
    )
    (net (code "11") (name "/PWM-OUT-OPTO-BH") (class "Default")
      (node (ref "OP3") (pin "6") (pinfunction "Vo_6") (pintype "passive"))
      (node (ref "R21") (pin "2") (pinfunction "2_2") (pintype "passive"))
      (node (ref "R28") (pin "2") (pinfunction "2_2") (pintype "passive"))
      (node (ref "U3") (pin "2") (pinfunction "HIN_2") (pintype "input"))
    )
    (net (code "12") (name "/PWM-OUT-OPTO-BL") (class "Default")
      (node (ref "OP4") (pin "6") (pinfunction "Vo_6") (pintype "passive"))
      (node (ref "R22") (pin "2") (pinfunction "2_2") (pintype "passive"))
      (node (ref "R30") (pin "2") (pinfunction "2_2") (pintype "passive"))
      (node (ref "U4") (pin "2") (pinfunction "HIN_2") (pintype "input"))
    )
    (net (code "13") (name "DRV_12V") (class "Default")
      (node (ref "C10") (pin "2") (pinfunction "2_2") (pintype "passive"))
      (node (ref "C26") (pin "2") (pinfunction "2_2") (pintype "passive"))
      (node (ref "C29") (pin "1") (pinfunction "+_1") (pintype "passive"))
      (node (ref "C3") (pin "2") (pinfunction "2_2") (pintype "passive"))
      (node (ref "C4") (pin "2") (pinfunction "2_2") (pintype "passive"))
      (node (ref "C9") (pin "2") (pinfunction "2_2") (pintype "passive"))
      (node (ref "CON3") (pin "2") (pinfunction "2_2") (pintype "passive"))
      (node (ref "D1") (pin "2") (pinfunction "A_2") (pintype "passive"))
      (node (ref "D15") (pin "2") (pinfunction "A_2") (pintype "passive"))
      (node (ref "D16") (pin "2") (pinfunction "A_2") (pintype "passive"))
      (node (ref "D2") (pin "2") (pinfunction "A_2") (pintype "passive"))
      (node (ref "U1") (pin "1") (pinfunction "VCC_1") (pintype "power_in"))
      (node (ref "U11") (pin "3") (pinfunction "VIN_3") (pintype "passive"))
      (node (ref "U2") (pin "1") (pinfunction "VCC_1") (pintype "power_in"))
      (node (ref "U3") (pin "1") (pinfunction "VCC_1") (pintype "power_in"))
      (node (ref "U4") (pin "1") (pinfunction "VCC_1") (pintype "power_in"))
    )
    (net (code "14") (name "GND_MCU") (class "Default")
      (node (ref "C15") (pin "1") (pinfunction "1_1") (pintype "passive"))
      (node (ref "C16") (pin "1") (pinfunction "1_1") (pintype "passive"))
      (node (ref "C21") (pin "1") (pinfunction "1_1") (pintype "passive"))
      (node (ref "C22") (pin "1") (pinfunction "1_1") (pintype "passive"))
      (node (ref "C28") (pin "2") (pinfunction "-_2") (pintype "passive"))
      (node (ref "CON3") (pin "3") (pinfunction "3_3") (pintype "passive"))
      (node (ref "Hall1") (pin "5") (pinfunction "GND_5") (pintype "passive"))
      (node (ref "Hall2") (pin "5") (pinfunction "GND_5") (pintype "passive"))
      (node (ref "TP3") (pin "1") (pinfunction "A_1") (pintype "passive"))
      (node (ref "TP4") (pin "1") (pinfunction "A_1") (pintype "passive"))
    )
    (net (code "15") (name "GND_MO") (class "Default")
      (node (ref "C10") (pin "1") (pinfunction "1_1") (pintype "passive"))
      (node (ref "C11") (pin "2") (pinfunction "-_2") (pintype "passive"))
      (node (ref "C12") (pin "2") (pinfunction "-_2") (pintype "passive"))
      (node (ref "C13") (pin "2") (pinfunction "2_2") (pintype "passive"))
      (node (ref "C14") (pin "2") (pinfunction "2_2") (pintype "passive"))
      (node (ref "C26") (pin "1") (pinfunction "1_1") (pintype "passive"))
      (node (ref "C27") (pin "1") (pinfunction "1_1") (pintype "passive"))
      (node (ref "C29") (pin "2") (pinfunction "-_2") (pintype "passive"))
      (node (ref "C3") (pin "1") (pinfunction "1_1") (pintype "passive"))
      (node (ref "C4") (pin "1") (pinfunction "1_1") (pintype "passive"))
      (node (ref "C5") (pin "2") (pinfunction "2_2") (pintype "passive"))
      (node (ref "C54") (pin "1") (pinfunction "1_1") (pintype "passive"))
      (node (ref "C6") (pin "2") (pinfunction "2_2") (pintype "passive"))
      (node (ref "C9") (pin "1") (pinfunction "1_1") (pintype "passive"))
      (node (ref "CON1") (pin "2") (pinfunction "2_2") (pintype "passive"))
      (node (ref "CON3") (pin "1") (pinfunction "1_1") (pintype "passive"))
      (node (ref "D13") (pin "2") (pinfunction "A_2") (pintype "passive"))
      (node (ref "D14") (pin "2") (pinfunction "A_2") (pintype "passive"))
      (node (ref "D27") (pin "2") (pinfunction "A_2") (pintype "passive"))
      (node (ref "D28") (pin "2") (pinfunction "A_2") (pintype "passive"))
      (node (ref "OP1") (pin "5") (pinfunction "GND_5") (pintype "passive"))
      (node (ref "OP2") (pin "5") (pinfunction "GND_5") (pintype "passive"))
      (node (ref "OP3") (pin "5") (pinfunction "GND_5") (pintype "passive"))
      (node (ref "OP4") (pin "5") (pinfunction "GND_5") (pintype "passive"))
      (node (ref "Q3") (pin "3") (pinfunction "S_3") (pintype "passive"))
      (node (ref "Q4") (pin "3") (pinfunction "S_3") (pintype "passive"))
      (node (ref "Q7") (pin "3") (pinfunction "S_3") (pintype "passive"))
      (node (ref "Q8") (pin "3") (pinfunction "S_3") (pintype "passive"))
      (node (ref "R10") (pin "2") (pinfunction "2_2") (pintype "passive"))
      (node (ref "R25") (pin "2") (pinfunction "2_2") (pintype "passive"))
      (node (ref "R26") (pin "2") (pinfunction "2_2") (pintype "passive"))
      (node (ref "R9") (pin "2") (pinfunction "2_2") (pintype "passive"))
      (node (ref "U1") (pin "4") (pinfunction "COM_4") (pintype "power_in"))
      (node (ref "U11") (pin "1") (pinfunction "GND_1") (pintype "passive"))
      (node (ref "U2") (pin "4") (pinfunction "COM_4") (pintype "power_in"))
      (node (ref "U3") (pin "4") (pinfunction "COM_4") (pintype "power_in"))
      (node (ref "U4") (pin "4") (pinfunction "COM_4") (pintype "power_in"))
    )
    (net (code "16") (name "HV+") (class "Default")
      (node (ref "C11") (pin "1") (pinfunction "+_1") (pintype "passive"))
      (node (ref "C12") (pin "1") (pinfunction "+_1") (pintype "passive"))
      (node (ref "CON1") (pin "1") (pinfunction "1_1") (pintype "passive"))
      (node (ref "Q1") (pin "2") (pinfunction "D_2") (pintype "passive"))
      (node (ref "Q2") (pin "2") (pinfunction "D_2") (pintype "passive"))
      (node (ref "Q5") (pin "2") (pinfunction "D_2") (pintype "passive"))
      (node (ref "Q6") (pin "2") (pinfunction "D_2") (pintype "passive"))
    )
    (net (code "17") (name "IA") (class "Default")
      (node (ref "Hall1") (pin "7") (pinfunction "OUT_7") (pintype "passive"))
      (node (ref "TP1") (pin "1") (pinfunction "A_1") (pintype "passive"))
    )
    (net (code "18") (name "IB") (class "Default")
      (node (ref "Hall2") (pin "7") (pinfunction "OUT_7") (pintype "passive"))
      (node (ref "TP2") (pin "1") (pinfunction "A_1") (pintype "passive"))
    )
    (net (code "19") (name "MCU_5V") (class "Default")
      (node (ref "C16") (pin "2") (pinfunction "2_2") (pintype "passive"))
      (node (ref "C22") (pin "2") (pinfunction "2_2") (pintype "passive"))
      (node (ref "C28") (pin "1") (pinfunction "+_1") (pintype "passive"))
      (node (ref "CON3") (pin "4") (pinfunction "4_4") (pintype "passive"))
      (node (ref "Hall1") (pin "8") (pinfunction "VCC_8") (pintype "passive"))
      (node (ref "Hall2") (pin "8") (pinfunction "VCC_8") (pintype "passive"))
    )
    (net (code "20") (name "Net-(D1-K)") (class "Default")
      (node (ref "C1") (pin "1") (pinfunction "1_1") (pintype "passive"))
      (node (ref "D1") (pin "1") (pinfunction "K_1") (pintype "passive"))
      (node (ref "U1") (pin "8") (pinfunction "VB_8") (pintype "power_in"))
    )
    (net (code "21") (name "Net-(D2-K)") (class "Default")
      (node (ref "C2") (pin "1") (pinfunction "1_1") (pintype "passive"))
      (node (ref "D2") (pin "1") (pinfunction "K_1") (pintype "passive"))
      (node (ref "U2") (pin "8") (pinfunction "VB_8") (pintype "power_in"))
    )
    (net (code "22") (name "Net-(D5-A)") (class "Default")
      (node (ref "D5") (pin "2") (pinfunction "A_2") (pintype "passive"))
      (node (ref "D7") (pin "1") (pinfunction "K_1") (pintype "passive"))
      (node (ref "Q1") (pin "1") (pinfunction "G_1") (pintype "passive"))
      (node (ref "R1") (pin "1") (pinfunction "1_1") (pintype "passive"))
      (node (ref "R3") (pin "1") (pinfunction "1_1") (pintype "passive"))
    )
    (net (code "23") (name "Net-(D5-K)") (class "Default")
      (node (ref "D5") (pin "1") (pinfunction "K_1") (pintype "passive"))
      (node (ref "R3") (pin "2") (pinfunction "2_2") (pintype "passive"))
      (node (ref "U1") (pin "7") (pinfunction "HO_7") (pintype "output"))
    )
    (net (code "24") (name "Net-(D6-A)") (class "Default")
      (node (ref "D6") (pin "2") (pinfunction "A_2") (pintype "passive"))
      (node (ref "D8") (pin "1") (pinfunction "K_1") (pintype "passive"))
      (node (ref "Q2") (pin "1") (pinfunction "G_1") (pintype "passive"))
      (node (ref "R2") (pin "1") (pinfunction "1_1") (pintype "passive"))
      (node (ref "R4") (pin "1") (pinfunction "1_1") (pintype "passive"))
    )
    (net (code "25") (name "Net-(D6-K)") (class "Default")
      (node (ref "D6") (pin "1") (pinfunction "K_1") (pintype "passive"))
      (node (ref "R4") (pin "2") (pinfunction "2_2") (pintype "passive"))
      (node (ref "U2") (pin "7") (pinfunction "HO_7") (pintype "output"))
    )
    (net (code "26") (name "Net-(D9-K)") (class "Default")
      (node (ref "D9") (pin "1") (pinfunction "K_1") (pintype "passive"))
      (node (ref "R7") (pin "2") (pinfunction "2_2") (pintype "passive"))
      (node (ref "U1") (pin "5") (pinfunction "LO_5") (pintype "output"))
    )
    (net (code "27") (name "Net-(D10-A)") (class "Default")
      (node (ref "D10") (pin "2") (pinfunction "A_2") (pintype "passive"))
      (node (ref "D14") (pin "1") (pinfunction "K_1") (pintype "passive"))
      (node (ref "Q4") (pin "1") (pinfunction "G_1") (pintype "passive"))
      (node (ref "R10") (pin "1") (pinfunction "1_1") (pintype "passive"))
      (node (ref "R8") (pin "1") (pinfunction "1_1") (pintype "passive"))
    )
    (net (code "28") (name "Net-(D10-K)") (class "Default")
      (node (ref "D10") (pin "1") (pinfunction "K_1") (pintype "passive"))
      (node (ref "R8") (pin "2") (pinfunction "2_2") (pintype "passive"))
      (node (ref "U2") (pin "5") (pinfunction "LO_5") (pintype "output"))
    )
    (net (code "29") (name "Net-(D13-K)") (class "Default")
      (node (ref "D13") (pin "1") (pinfunction "K_1") (pintype "passive"))
      (node (ref "D9") (pin "2") (pinfunction "A_2") (pintype "passive"))
      (node (ref "Q3") (pin "1") (pinfunction "G_1") (pintype "passive"))
      (node (ref "R7") (pin "1") (pinfunction "1_1") (pintype "passive"))
      (node (ref "R9") (pin "1") (pinfunction "1_1") (pintype "passive"))
    )
    (net (code "30") (name "Net-(D15-K)") (class "Default")
      (node (ref "C7") (pin "1") (pinfunction "1_1") (pintype "passive"))
      (node (ref "D15") (pin "1") (pinfunction "K_1") (pintype "passive"))
      (node (ref "U3") (pin "8") (pinfunction "VB_8") (pintype "power_in"))
    )
    (net (code "31") (name "Net-(D16-K)") (class "Default")
      (node (ref "C8") (pin "1") (pinfunction "1_1") (pintype "passive"))
      (node (ref "D16") (pin "1") (pinfunction "K_1") (pintype "passive"))
      (node (ref "U4") (pin "8") (pinfunction "VB_8") (pintype "power_in"))
    )
    (net (code "32") (name "Net-(D19-A)") (class "Default")
      (node (ref "D19") (pin "2") (pinfunction "A_2") (pintype "passive"))
      (node (ref "D21") (pin "1") (pinfunction "K_1") (pintype "passive"))
      (node (ref "Q5") (pin "1") (pinfunction "G_1") (pintype "passive"))
      (node (ref "R17") (pin "1") (pinfunction "1_1") (pintype "passive"))
      (node (ref "R19") (pin "1") (pinfunction "1_1") (pintype "passive"))
    )
    (net (code "33") (name "Net-(D19-K)") (class "Default")
      (node (ref "D19") (pin "1") (pinfunction "K_1") (pintype "passive"))
      (node (ref "R19") (pin "2") (pinfunction "2_2") (pintype "passive"))
      (node (ref "U3") (pin "7") (pinfunction "HO_7") (pintype "output"))
    )
    (net (code "34") (name "Net-(D20-A)") (class "Default")
      (node (ref "D20") (pin "2") (pinfunction "A_2") (pintype "passive"))
      (node (ref "D22") (pin "1") (pinfunction "K_1") (pintype "passive"))
      (node (ref "Q6") (pin "1") (pinfunction "G_1") (pintype "passive"))
      (node (ref "R18") (pin "1") (pinfunction "1_1") (pintype "passive"))
      (node (ref "R20") (pin "1") (pinfunction "1_1") (pintype "passive"))
    )
    (net (code "35") (name "Net-(D20-K)") (class "Default")
      (node (ref "D20") (pin "1") (pinfunction "K_1") (pintype "passive"))
      (node (ref "R20") (pin "2") (pinfunction "2_2") (pintype "passive"))
      (node (ref "U4") (pin "7") (pinfunction "HO_7") (pintype "output"))
    )
    (net (code "36") (name "Net-(D23-A)") (class "Default")
      (node (ref "D23") (pin "2") (pinfunction "A_2") (pintype "passive"))
      (node (ref "D27") (pin "1") (pinfunction "K_1") (pintype "passive"))
      (node (ref "Q7") (pin "1") (pinfunction "G_1") (pintype "passive"))
      (node (ref "R23") (pin "1") (pinfunction "1_1") (pintype "passive"))
      (node (ref "R25") (pin "1") (pinfunction "1_1") (pintype "passive"))
    )
    (net (code "37") (name "Net-(D23-K)") (class "Default")
      (node (ref "D23") (pin "1") (pinfunction "K_1") (pintype "passive"))
      (node (ref "R23") (pin "2") (pinfunction "2_2") (pintype "passive"))
      (node (ref "U3") (pin "5") (pinfunction "LO_5") (pintype "output"))
    )
    (net (code "38") (name "Net-(D24-A)") (class "Default")
      (node (ref "D24") (pin "2") (pinfunction "A_2") (pintype "passive"))
      (node (ref "D28") (pin "1") (pinfunction "K_1") (pintype "passive"))
      (node (ref "Q8") (pin "1") (pinfunction "G_1") (pintype "passive"))
      (node (ref "R24") (pin "1") (pinfunction "1_1") (pintype "passive"))
      (node (ref "R26") (pin "1") (pinfunction "1_1") (pintype "passive"))
    )
    (net (code "39") (name "Net-(D24-K)") (class "Default")
      (node (ref "D24") (pin "1") (pinfunction "K_1") (pintype "passive"))
      (node (ref "R24") (pin "2") (pinfunction "2_2") (pintype "passive"))
      (node (ref "U4") (pin "5") (pinfunction "LO_5") (pintype "output"))
    )
    (net (code "40") (name "Net-(Hall1-FILTER)") (class "Default")
      (node (ref "C15") (pin "2") (pinfunction "2_2") (pintype "passive"))
      (node (ref "Hall1") (pin "6") (pinfunction "FILTER_6") (pintype "passive"))
    )
    (net (code "41") (name "Net-(Hall2-FILTER)") (class "Default")
      (node (ref "C21") (pin "2") (pinfunction "2_2") (pintype "passive"))
      (node (ref "Hall2") (pin "6") (pinfunction "FILTER_6") (pintype "passive"))
    )
    (net (code "42") (name "Net-(OP1-A)") (class "Default")
      (node (ref "OP1") (pin "2") (pinfunction "A_2") (pintype "passive"))
      (node (ref "R15") (pin "2") (pinfunction "2_2") (pintype "passive"))
    )
    (net (code "43") (name "Net-(OP2-A)") (class "Default")
      (node (ref "OP2") (pin "2") (pinfunction "A_2") (pintype "passive"))
      (node (ref "R16") (pin "1") (pinfunction "1_1") (pintype "passive"))
    )
    (net (code "44") (name "Net-(OP3-A)") (class "Default")
      (node (ref "OP3") (pin "2") (pinfunction "A_2") (pintype "passive"))
      (node (ref "R31") (pin "2") (pinfunction "2_2") (pintype "passive"))
    )
    (net (code "45") (name "Net-(OP4-A)") (class "Default")
      (node (ref "OP4") (pin "2") (pinfunction "A_2") (pintype "passive"))
      (node (ref "R32") (pin "1") (pinfunction "1_1") (pintype "passive"))
    )
    (net (code "46") (name "Net-(U1-~{LIN})") (class "Default")
      (node (ref "R5") (pin "1") (pinfunction "1_1") (pintype "passive"))
      (node (ref "U1") (pin "3") (pinfunction "~{LIN}_3") (pintype "input"))
    )
    (net (code "47") (name "Net-(U2-~{LIN})") (class "Default")
      (node (ref "R6") (pin "1") (pinfunction "1_1") (pintype "passive"))
      (node (ref "U2") (pin "3") (pinfunction "~{LIN}_3") (pintype "input"))
    )
    (net (code "48") (name "Net-(U3-~{LIN})") (class "Default")
      (node (ref "R21") (pin "1") (pinfunction "1_1") (pintype "passive"))
      (node (ref "U3") (pin "3") (pinfunction "~{LIN}_3") (pintype "input"))
    )
    (net (code "49") (name "Net-(U4-~{LIN})") (class "Default")
      (node (ref "R22") (pin "1") (pinfunction "1_1") (pintype "passive"))
      (node (ref "U4") (pin "3") (pinfunction "~{LIN}_3") (pintype "input"))
    )
    (net (code "50") (name "OP_5V") (class "Default")
      (node (ref "C13") (pin "1") (pinfunction "1_1") (pintype "passive"))
      (node (ref "C14") (pin "1") (pinfunction "1_1") (pintype "passive"))
      (node (ref "C27") (pin "2") (pinfunction "2_2") (pintype "passive"))
      (node (ref "C5") (pin "1") (pinfunction "1_1") (pintype "passive"))
      (node (ref "C54") (pin "2") (pinfunction "2_2") (pintype "passive"))
      (node (ref "C6") (pin "1") (pinfunction "1_1") (pintype "passive"))
      (node (ref "OP1") (pin "7") (pinfunction "VE_7") (pintype "passive"))
      (node (ref "OP1") (pin "8") (pinfunction "VCC_8") (pintype "passive"))
      (node (ref "OP2") (pin "7") (pinfunction "VE_7") (pintype "passive"))
      (node (ref "OP2") (pin "8") (pinfunction "VCC_8") (pintype "passive"))
      (node (ref "OP3") (pin "7") (pinfunction "VE_7") (pintype "passive"))
      (node (ref "OP3") (pin "8") (pinfunction "VCC_8") (pintype "passive"))
      (node (ref "OP4") (pin "7") (pinfunction "VE_7") (pintype "passive"))
      (node (ref "OP4") (pin "8") (pinfunction "VCC_8") (pintype "passive"))
      (node (ref "R12") (pin "1") (pinfunction "1_1") (pintype "passive"))
      (node (ref "R14") (pin "1") (pinfunction "1_1") (pintype "passive"))
      (node (ref "R28") (pin "1") (pinfunction "1_1") (pintype "passive"))
      (node (ref "R30") (pin "1") (pinfunction "1_1") (pintype "passive"))
      (node (ref "U11") (pin "2") (pinfunction "VOUT_2") (pintype "passive"))
      (node (ref "U11") (pin "4") (pinfunction "VOUT_4") (pintype "passive"))
    )
    (net (code "51") (name "PWM-IN-OPTO-AH") (class "Default")
      (node (ref "OP1") (pin "3") (pinfunction "C_3") (pintype "passive"))
    )
    (net (code "52") (name "PWM-IN-OPTO-AL") (class "Default")
      (node (ref "OP2") (pin "3") (pinfunction "C_3") (pintype "passive"))
    )
    (net (code "53") (name "PWM-IN-OPTO-BH") (class "Default")
      (node (ref "OP3") (pin "3") (pinfunction "C_3") (pintype "passive"))
    )
    (net (code "54") (name "PWM-IN-OPTO-BL") (class "Default")
      (node (ref "OP4") (pin "3") (pinfunction "C_3") (pintype "passive"))
    )
    (net (code "55") (name "unconnected-(CON3-Pad5)") (class "Default")
      (node (ref "CON3") (pin "5") (pinfunction "5_5") (pintype "passive"))
    )
    (net (code "56") (name "unconnected-(OP1-N{slash}C-Pad1)") (class "Default")
      (node (ref "OP1") (pin "1") (pinfunction "N/C_1") (pintype "passive"))
    )
    (net (code "57") (name "unconnected-(OP1-N{slash}C-Pad4)") (class "Default")
      (node (ref "OP1") (pin "4") (pinfunction "N/C_4") (pintype "passive"))
    )
    (net (code "58") (name "unconnected-(OP2-N{slash}C-Pad1)") (class "Default")
      (node (ref "OP2") (pin "1") (pinfunction "N/C_1") (pintype "passive"))
    )
    (net (code "59") (name "unconnected-(OP2-N{slash}C-Pad4)") (class "Default")
      (node (ref "OP2") (pin "4") (pinfunction "N/C_4") (pintype "passive"))
    )
    (net (code "60") (name "unconnected-(OP3-N{slash}C-Pad1)") (class "Default")
      (node (ref "OP3") (pin "1") (pinfunction "N/C_1") (pintype "passive"))
    )
    (net (code "61") (name "unconnected-(OP3-N{slash}C-Pad4)") (class "Default")
      (node (ref "OP3") (pin "4") (pinfunction "N/C_4") (pintype "passive"))
    )
    (net (code "62") (name "unconnected-(OP4-N{slash}C-Pad1)") (class "Default")
      (node (ref "OP4") (pin "1") (pinfunction "N/C_1") (pintype "passive"))
    )
    (net (code "63") (name "unconnected-(OP4-N{slash}C-Pad4)") (class "Default")
      (node (ref "OP4") (pin "4") (pinfunction "N/C_4") (pintype "passive"))
    )
  )
)
